# Sheet1.net
KiCad netlist of a schematic drawn in Altium Designer
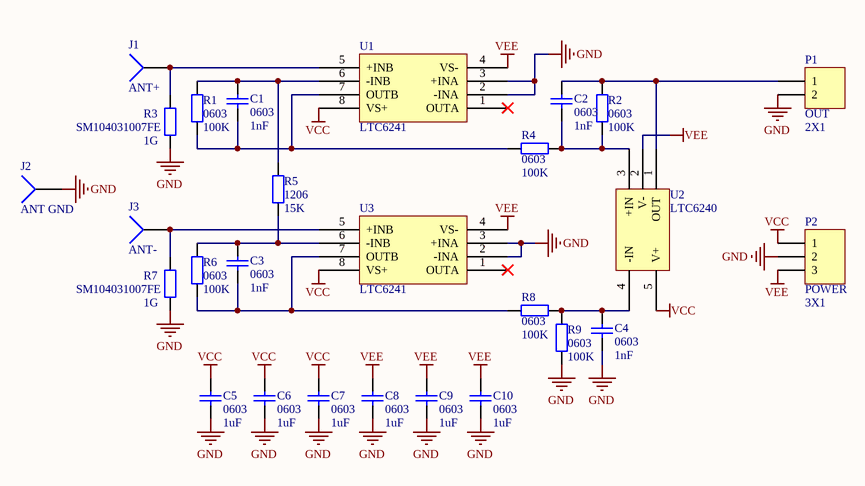
[diagram p0: Sheet1.SchDoc]

(export (version "E")
  (design (tool "Eeschema 10.0.6"))
  (components
    (comp (ref "C1")
      (value "0603")
      (footprint "1608[0603]")
      (description "Capacitor")
      (fields (field (name "ALTIUM_VALUE") "1nF"))
      (libsource (lib "Miscellaneous Devices Local Copy") (part "Cap"))
    )
    (comp (ref "C2")
      (value "0603")
      (footprint "1608[0603]")
      (description "Capacitor")
      (fields (field (name "ALTIUM_VALUE") "1nF"))
      (libsource (lib "Miscellaneous Devices Local Copy") (part "Cap"))
    )
    (comp (ref "C3")
      (value "0603")
      (footprint "1608[0603]")
      (description "Capacitor")
      (fields (field (name "ALTIUM_VALUE") "1nF"))
      (libsource (lib "Miscellaneous Devices Local Copy") (part "Cap"))
    )
    (comp (ref "C4")
      (value "0603")
      (footprint "1608[0603]")
      (description "Capacitor")
      (fields (field (name "ALTIUM_VALUE") "1nF"))
      (libsource (lib "Miscellaneous Devices Local Copy") (part "Cap"))
    )
    (comp (ref "C5")
      (value "0603")
      (footprint "1608[0603]")
      (description "Capacitor")
      (fields (field (name "ALTIUM_VALUE") "1uF"))
      (libsource (lib "Miscellaneous Devices Local Copy") (part "Cap"))
    )
    (comp (ref "C6")
      (value "0603")
      (footprint "1608[0603]")
      (description "Capacitor")
      (fields (field (name "ALTIUM_VALUE") "1uF"))
      (libsource (lib "Miscellaneous Devices Local Copy") (part "Cap"))
    )
    (comp (ref "C7")
      (value "0603")
      (footprint "1608[0603]")
      (description "Capacitor")
      (fields (field (name "ALTIUM_VALUE") "1uF"))
      (libsource (lib "Miscellaneous Devices Local Copy") (part "Cap"))
    )
    (comp (ref "C8")
      (value "0603")
      (footprint "1608[0603]")
      (description "Capacitor")
      (fields (field (name "ALTIUM_VALUE") "1uF"))
      (libsource (lib "Miscellaneous Devices Local Copy") (part "Cap"))
    )
    (comp (ref "C9")
      (value "0603")
      (footprint "1608[0603]")
      (description "Capacitor")
      (fields (field (name "ALTIUM_VALUE") "1uF"))
      (libsource (lib "Miscellaneous Devices Local Copy") (part "Cap"))
    )
    (comp (ref "C10")
      (value "0603")
      (footprint "1608[0603]")
      (description "Capacitor")
      (fields (field (name "ALTIUM_VALUE") "1uF"))
      (libsource (lib "Miscellaneous Devices Local Copy") (part "Cap"))
    )
    (comp (ref "J1")
      (value "ANT+")
      (footprint "PIN1")
      (description "Socket")
      (libsource (lib "Miscellaneous Connectors Local Copy") (part "Socket"))
    )
    (comp (ref "J2")
      (value "ANT GND")
      (footprint "PIN1")
      (description "Socket")
      (libsource (lib "Miscellaneous Connectors Local Copy") (part "Socket"))
    )
    (comp (ref "J3")
      (value "ANT-")
      (footprint "PIN1")
      (description "Socket")
      (libsource (lib "Miscellaneous Connectors Local Copy") (part "Socket"))
    )
    (comp (ref "P1")
      (value "OUT")
      (footprint "HDR1X2")
      (description "Header, 2-Pin")
      (fields (field (name "ALTIUM_VALUE") "2X1"))
      (libsource (lib "Miscellaneous Connectors Local Copy") (part "Header 2"))
    )
    (comp (ref "P2")
      (value "POWER")
      (footprint "HDR1X3")
      (description "Header, 3-Pin")
      (fields (field (name "ALTIUM_VALUE") "3X1"))
      (libsource (lib "Miscellaneous Connectors Local Copy") (part "Header 3"))
    )
    (comp (ref "R1")
      (value "0603")
      (footprint "1608[0603]")
      (description "Resistor")
      (fields (field (name "ALTIUM_VALUE") "100K"))
      (libsource (lib "Miscellaneous Devices Local Copy") (part "Res2"))
    )
    (comp (ref "R2")
      (value "0603")
      (footprint "1608[0603]")
      (description "Resistor")
      (fields (field (name "ALTIUM_VALUE") "100K"))
      (libsource (lib "") (part "Res2_2"))
    )
    (comp (ref "R3")
      (value "SM104031007FE")
      (footprint "OHMITE_SM104031007FE_ThroughHoleResistor")
      (description "Resistor")
      (fields (field (name "ALTIUM_VALUE") "1G"))
      (libsource (lib "") (part "Res2_2"))
    )
    (comp (ref "R4")
      (value "0603")
      (footprint "1608[0603]")
      (description "Resistor")
      (fields (field (name "ALTIUM_VALUE") "100K"))
      (libsource (lib "") (part "Res2_1"))
    )
    (comp (ref "R5")
      (value "1206")
      (footprint "C1206")
      (description "Resistor")
      (fields (field (name "ALTIUM_VALUE") "15K"))
      (libsource (lib "") (part "Res2_2"))
    )
    (comp (ref "R6")
      (value "0603")
      (footprint "1608[0603]")
      (description "Resistor")
      (fields (field (name "ALTIUM_VALUE") "100K"))
      (libsource (lib "Miscellaneous Devices Local Copy") (part "Res2"))
    )
    (comp (ref "R7")
      (value "SM104031007FE")
      (footprint "OHMITE_SM104031007FE_ThroughHoleResistor")
      (description "Resistor")
      (fields (field (name "ALTIUM_VALUE") "1G"))
      (libsource (lib "") (part "Res2_2"))
    )
    (comp (ref "R8")
      (value "0603")
      (footprint "1608[0603]")
      (description "Resistor")
      (fields (field (name "ALTIUM_VALUE") "100K"))
      (libsource (lib "") (part "Res2_1"))
    )
    (comp (ref "R9")
      (value "0603")
      (footprint "1608[0603]")
      (description "Resistor")
      (fields (field (name "ALTIUM_VALUE") "100K"))
      (libsource (lib "Miscellaneous Devices Local Copy") (part "Res2"))
    )
    (comp (ref "U1")
      (value "LTC6241")
      (footprint "LTC6241_SOIC8")
      (description "low noise, high input impedance opamp")
      (libsource (lib "Schlib1") (part "LTC6241"))
    )
    (comp (ref "U2")
      (value "LTC6240")
      (footprint "LTC6240_SOT23")
      (description "low noise jfet opamp")
      (libsource (lib "Schlib1") (part "LTC6240"))
    )
    (comp (ref "U3")
      (value "LTC6241")
      (footprint "LTC6241_SOIC8")
      (description "low noise, high input impedance opamp")
      (libsource (lib "Schlib1") (part "LTC6241"))
    )
  )
  (nets
    (net (code "1") (name "GND") (class "Default")
      (node (ref "C10") (pin "1") (pinfunction "1_1") (pintype "passive"))
      (node (ref "C4") (pin "1") (pinfunction "1_1") (pintype "passive"))
      (node (ref "C5") (pin "1") (pinfunction "1_1") (pintype "passive"))
      (node (ref "C6") (pin "1") (pinfunction "1_1") (pintype "passive"))
      (node (ref "C7") (pin "1") (pinfunction "1_1") (pintype "passive"))
      (node (ref "C8") (pin "1") (pinfunction "1_1") (pintype "passive"))
      (node (ref "C9") (pin "1") (pinfunction "1_1") (pintype "passive"))
      (node (ref "J2") (pin "1") (pinfunction "1_1") (pintype "passive"))
      (node (ref "P1") (pin "2") (pinfunction "2_2") (pintype "passive"))
      (node (ref "P2") (pin "2") (pinfunction "2_2") (pintype "passive"))
      (node (ref "R3") (pin "1") (pinfunction "1_1") (pintype "passive"))
      (node (ref "R7") (pin "1") (pinfunction "1_1") (pintype "passive"))
      (node (ref "R9") (pin "2") (pinfunction "2_2") (pintype "passive"))
      (node (ref "U1") (pin "2") (pinfunction "-INA_2") (pintype "passive"))
      (node (ref "U1") (pin "3") (pinfunction "+INA_3") (pintype "passive"))
      (node (ref "U3") (pin "2") (pinfunction "-INA_2") (pintype "passive"))
      (node (ref "U3") (pin "3") (pinfunction "+INA_3") (pintype "passive"))
    )
    (net (code "2") (name "Net-(U1-+INB)") (class "Default")
      (node (ref "J1") (pin "1") (pinfunction "1_1") (pintype "passive"))
      (node (ref "R3") (pin "2") (pinfunction "2_2") (pintype "passive"))
      (node (ref "U1") (pin "5") (pinfunction "+INB_5") (pintype "passive"))
    )
    (net (code "3") (name "Net-(U1--INB)") (class "Default")
      (node (ref "C1") (pin "2") (pinfunction "2_2") (pintype "passive"))
      (node (ref "R1") (pin "1") (pinfunction "1_1") (pintype "passive"))
      (node (ref "R5") (pin "2") (pinfunction "2_2") (pintype "passive"))
      (node (ref "U1") (pin "6") (pinfunction "-INB_6") (pintype "passive"))
    )
    (net (code "4") (name "Net-(U1-OUTB)") (class "Default")
      (node (ref "C1") (pin "1") (pinfunction "1_1") (pintype "passive"))
      (node (ref "R1") (pin "2") (pinfunction "2_2") (pintype "passive"))
      (node (ref "R4") (pin "1") (pinfunction "1_1") (pintype "passive"))
      (node (ref "U1") (pin "7") (pinfunction "OUTB_7") (pintype "passive"))
    )
    (net (code "5") (name "Net-(U2-+IN)") (class "Default")
      (node (ref "C2") (pin "2") (pinfunction "2_2") (pintype "passive"))
      (node (ref "R2") (pin "1") (pinfunction "1_1") (pintype "passive"))
      (node (ref "R4") (pin "2") (pinfunction "2_2") (pintype "passive"))
      (node (ref "U2") (pin "3") (pinfunction "+IN_3") (pintype "passive"))
    )
    (net (code "6") (name "Net-(U2--IN)") (class "Default")
      (node (ref "C4") (pin "2") (pinfunction "2_2") (pintype "passive"))
      (node (ref "R8") (pin "2") (pinfunction "2_2") (pintype "passive"))
      (node (ref "R9") (pin "1") (pinfunction "1_1") (pintype "passive"))
      (node (ref "U2") (pin "4") (pinfunction "-IN_4") (pintype "passive"))
    )
    (net (code "7") (name "Net-(U2-OUT)") (class "Default")
      (node (ref "C2") (pin "1") (pinfunction "1_1") (pintype "passive"))
      (node (ref "P1") (pin "1") (pinfunction "1_1") (pintype "passive"))
      (node (ref "R2") (pin "2") (pinfunction "2_2") (pintype "passive"))
      (node (ref "U2") (pin "1") (pinfunction "OUT_1") (pintype "passive"))
    )
    (net (code "8") (name "Net-(U3-+INB)") (class "Default")
      (node (ref "J3") (pin "1") (pinfunction "1_1") (pintype "passive"))
      (node (ref "R7") (pin "2") (pinfunction "2_2") (pintype "passive"))
      (node (ref "U3") (pin "5") (pinfunction "+INB_5") (pintype "passive"))
    )
    (net (code "9") (name "Net-(U3--INB)") (class "Default")
      (node (ref "C3") (pin "2") (pinfunction "2_2") (pintype "passive"))
      (node (ref "R5") (pin "1") (pinfunction "1_1") (pintype "passive"))
      (node (ref "R6") (pin "1") (pinfunction "1_1") (pintype "passive"))
      (node (ref "U3") (pin "6") (pinfunction "-INB_6") (pintype "passive"))
    )
    (net (code "10") (name "Net-(U3-OUTB)") (class "Default")
      (node (ref "C3") (pin "1") (pinfunction "1_1") (pintype "passive"))
      (node (ref "R6") (pin "2") (pinfunction "2_2") (pintype "passive"))
      (node (ref "R8") (pin "1") (pinfunction "1_1") (pintype "passive"))
      (node (ref "U3") (pin "7") (pinfunction "OUTB_7") (pintype "passive"))
    )
    (net (code "11") (name "VCC") (class "Default")
      (node (ref "C5") (pin "2") (pinfunction "2_2") (pintype "passive"))
      (node (ref "C6") (pin "2") (pinfunction "2_2") (pintype "passive"))
      (node (ref "C7") (pin "2") (pinfunction "2_2") (pintype "passive"))
      (node (ref "P2") (pin "1") (pinfunction "1_1") (pintype "passive"))
      (node (ref "U1") (pin "8") (pinfunction "VS+_8") (pintype "passive"))
      (node (ref "U2") (pin "5") (pinfunction "V+_5") (pintype "passive"))
      (node (ref "U3") (pin "8") (pinfunction "VS+_8") (pintype "passive"))
    )
    (net (code "12") (name "VEE") (class "Default")
      (node (ref "C10") (pin "2") (pinfunction "2_2") (pintype "passive"))
      (node (ref "C8") (pin "2") (pinfunction "2_2") (pintype "passive"))
      (node (ref "C9") (pin "2") (pinfunction "2_2") (pintype "passive"))
      (node (ref "P2") (pin "3") (pinfunction "3_3") (pintype "passive"))
      (node (ref "U1") (pin "4") (pinfunction "VS-_4") (pintype "passive"))
      (node (ref "U2") (pin "2") (pinfunction "V-_2") (pintype "passive"))
      (node (ref "U3") (pin "4") (pinfunction "VS-_4") (pintype "passive"))
    )
    (net (code "13") (name "unconnected-(U1-OUTA-Pad1)") (class "Default")
      (node (ref "U1") (pin "1") (pinfunction "OUTA_1") (pintype "passive+no_connect"))
    )
    (net (code "14") (name "unconnected-(U3-OUTA-Pad1)") (class "Default")
      (node (ref "U3") (pin "1") (pinfunction "OUTA_1") (pintype "passive+no_connect"))
    )
  )
)
